# led_board.net
KiCad netlist of a schematic drawn in EAGLE
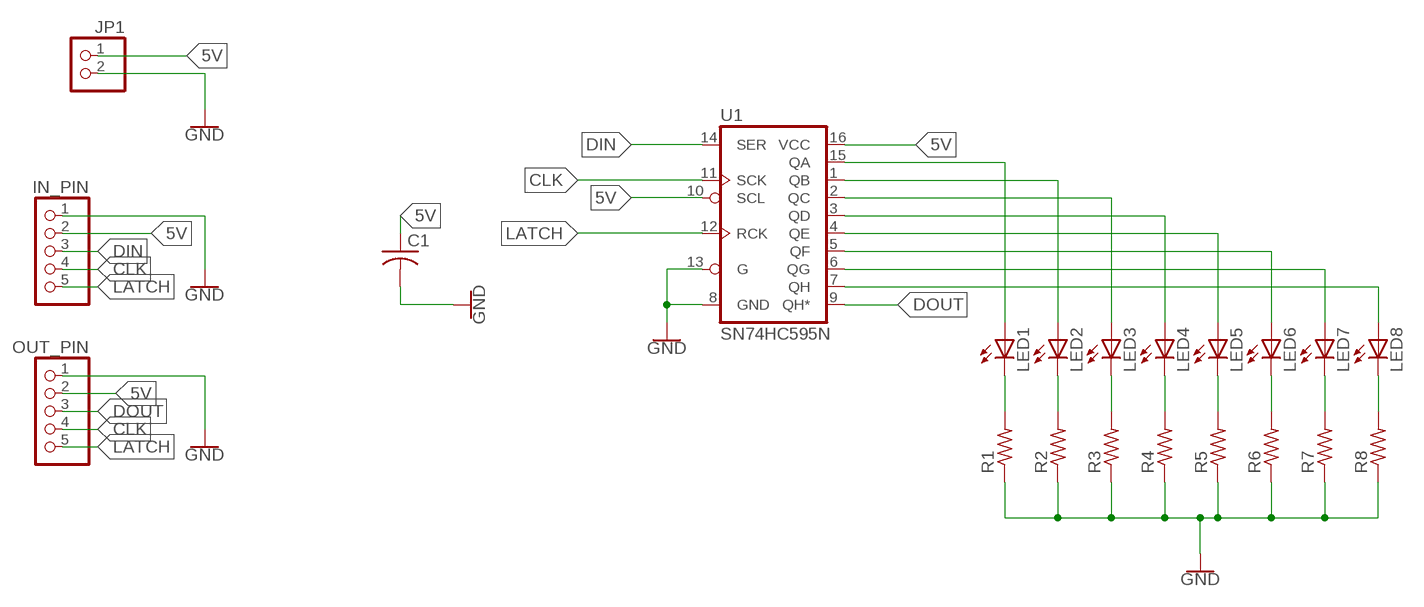
[diagram p0: schematic, sheet 1]

(export (version "E")
  (design (tool "Eeschema 10.0.6"))
  (components
    (comp (ref "C1")
      (value "C-US025-030X050")
      (footprint "eagle-import:C025-030X050")
      (libsource (lib "eagle-import") (part "C-US025-030X050"))
    )
    (comp (ref "IN_PIN")
      (value "PINHD-1X5")
      (footprint "eagle-import:1X05")
      (libsource (lib "eagle-import") (part "PINHD-1X5"))
    )
    (comp (ref "JP1")
      (value "PINHD-1X2")
      (footprint "eagle-import:1X02")
      (libsource (lib "eagle-import") (part "PINHD-1X2"))
    )
    (comp (ref "LED1")
      (value "LED3MM")
      (footprint "eagle-import:LED3MM")
      (libsource (lib "eagle-import") (part "LED3MM"))
    )
    (comp (ref "LED2")
      (value "LED3MM")
      (footprint "eagle-import:LED3MM")
      (libsource (lib "eagle-import") (part "LED3MM"))
    )
    (comp (ref "LED3")
      (value "LED3MM")
      (footprint "eagle-import:LED3MM")
      (libsource (lib "eagle-import") (part "LED3MM"))
    )
    (comp (ref "LED4")
      (value "LED3MM")
      (footprint "eagle-import:LED3MM")
      (libsource (lib "eagle-import") (part "LED3MM"))
    )
    (comp (ref "LED5")
      (value "LED3MM")
      (footprint "eagle-import:LED3MM")
      (libsource (lib "eagle-import") (part "LED3MM"))
    )
    (comp (ref "LED6")
      (value "LED3MM")
      (footprint "eagle-import:LED3MM")
      (libsource (lib "eagle-import") (part "LED3MM"))
    )
    (comp (ref "LED7")
      (value "LED3MM")
      (footprint "eagle-import:LED3MM")
      (libsource (lib "eagle-import") (part "LED3MM"))
    )
    (comp (ref "LED8")
      (value "LED3MM")
      (footprint "eagle-import:LED3MM")
      (libsource (lib "eagle-import") (part "LED3MM"))
    )
    (comp (ref "OUT_PIN")
      (value "PINHD-1X5")
      (footprint "eagle-import:1X05")
      (libsource (lib "eagle-import") (part "PINHD-1X5"))
    )
    (comp (ref "R1")
      (value "R-US_0207/7")
      (footprint "eagle-import:0207_7")
      (libsource (lib "eagle-import") (part "R-US_0207/7"))
    )
    (comp (ref "R2")
      (value "R-US_0207/7")
      (footprint "eagle-import:0207_7")
      (libsource (lib "eagle-import") (part "R-US_0207/7"))
    )
    (comp (ref "R3")
      (value "R-US_0207/7")
      (footprint "eagle-import:0207_7")
      (libsource (lib "eagle-import") (part "R-US_0207/7"))
    )
    (comp (ref "R4")
      (value "R-US_0207/7")
      (footprint "eagle-import:0207_7")
      (libsource (lib "eagle-import") (part "R-US_0207/7"))
    )
    (comp (ref "R5")
      (value "R-US_0207/7")
      (footprint "eagle-import:0207_7")
      (libsource (lib "eagle-import") (part "R-US_0207/7"))
    )
    (comp (ref "R6")
      (value "R-US_0207/7")
      (footprint "eagle-import:0207_7")
      (libsource (lib "eagle-import") (part "R-US_0207/7"))
    )
    (comp (ref "R7")
      (value "R-US_0207/7")
      (footprint "eagle-import:0207_7")
      (libsource (lib "eagle-import") (part "R-US_0207/7"))
    )
    (comp (ref "R8")
      (value "R-US_0207/7")
      (footprint "eagle-import:0207_7")
      (libsource (lib "eagle-import") (part "R-US_0207/7"))
    )
    (comp (ref "U1")
      (value "SN74HC595N")
      (footprint "eagle-import:DIP16")
      (libsource (lib "eagle-import") (part "74595NHC"))
    )
  )
  (nets
    (net (code "1") (name "5V") (class "Default")
      (node (ref "C1") (pin "1") (pinfunction "1_1") (pintype "passive"))
      (node (ref "IN_PIN") (pin "2") (pinfunction "2_2") (pintype "passive"))
      (node (ref "JP1") (pin "1") (pinfunction "1_1") (pintype "passive"))
      (node (ref "OUT_PIN") (pin "2") (pinfunction "2_2") (pintype "passive"))
      (node (ref "U1") (pin "10") (pinfunction "SCL_10") (pintype "input"))
      (node (ref "U1") (pin "16") (pinfunction "VCC_16") (pintype "power_in"))
    )
    (net (code "2") (name "CLK") (class "Default")
      (node (ref "IN_PIN") (pin "4") (pinfunction "4_4") (pintype "passive"))
      (node (ref "OUT_PIN") (pin "4") (pinfunction "4_4") (pintype "passive"))
      (node (ref "U1") (pin "11") (pinfunction "SCK_11") (pintype "input"))
    )
    (net (code "3") (name "DIN") (class "Default")
      (node (ref "IN_PIN") (pin "3") (pinfunction "3_3") (pintype "passive"))
      (node (ref "U1") (pin "14") (pinfunction "SER_14") (pintype "input"))
    )
    (net (code "4") (name "DOUT") (class "Default")
      (node (ref "OUT_PIN") (pin "3") (pinfunction "3_3") (pintype "passive"))
      (node (ref "U1") (pin "9") (pinfunction "QH*_9") (pintype "tri_state"))
    )
    (net (code "5") (name "GND") (class "Default")
      (node (ref "C1") (pin "2") (pinfunction "2_2") (pintype "passive"))
      (node (ref "IN_PIN") (pin "1") (pinfunction "1_1") (pintype "passive"))
      (node (ref "JP1") (pin "2") (pinfunction "2_2") (pintype "passive"))
      (node (ref "OUT_PIN") (pin "1") (pinfunction "1_1") (pintype "passive"))
      (node (ref "R1") (pin "1") (pinfunction "1_1") (pintype "passive"))
      (node (ref "R2") (pin "1") (pinfunction "1_1") (pintype "passive"))
      (node (ref "R3") (pin "1") (pinfunction "1_1") (pintype "passive"))
      (node (ref "R4") (pin "1") (pinfunction "1_1") (pintype "passive"))
      (node (ref "R5") (pin "1") (pinfunction "1_1") (pintype "passive"))
      (node (ref "R6") (pin "1") (pinfunction "1_1") (pintype "passive"))
      (node (ref "R7") (pin "1") (pinfunction "1_1") (pintype "passive"))
      (node (ref "R8") (pin "1") (pinfunction "1_1") (pintype "passive"))
      (node (ref "U1") (pin "13") (pinfunction "G_13") (pintype "input"))
      (node (ref "U1") (pin "8") (pinfunction "GND_8") (pintype "power_in"))
    )
    (net (code "6") (name "LATCH") (class "Default")
      (node (ref "IN_PIN") (pin "5") (pinfunction "5_5") (pintype "passive"))
      (node (ref "OUT_PIN") (pin "5") (pinfunction "5_5") (pintype "passive"))
      (node (ref "U1") (pin "12") (pinfunction "RCK_12") (pintype "input"))
    )
    (net (code "7") (name "Net-(LED1-C)") (class "Default")
      (node (ref "LED1") (pin "K") (pinfunction "C_K") (pintype "passive"))
      (node (ref "R1") (pin "2") (pinfunction "2_2") (pintype "passive"))
    )
    (net (code "8") (name "Net-(LED2-C)") (class "Default")
      (node (ref "LED2") (pin "K") (pinfunction "C_K") (pintype "passive"))
      (node (ref "R2") (pin "2") (pinfunction "2_2") (pintype "passive"))
    )
    (net (code "9") (name "Net-(LED3-C)") (class "Default")
      (node (ref "LED3") (pin "K") (pinfunction "C_K") (pintype "passive"))
      (node (ref "R3") (pin "2") (pinfunction "2_2") (pintype "passive"))
    )
    (net (code "10") (name "Net-(LED4-C)") (class "Default")
      (node (ref "LED4") (pin "K") (pinfunction "C_K") (pintype "passive"))
      (node (ref "R4") (pin "2") (pinfunction "2_2") (pintype "passive"))
    )
    (net (code "11") (name "Net-(LED5-C)") (class "Default")
      (node (ref "LED5") (pin "K") (pinfunction "C_K") (pintype "passive"))
      (node (ref "R5") (pin "2") (pinfunction "2_2") (pintype "passive"))
    )
    (net (code "12") (name "Net-(LED6-C)") (class "Default")
      (node (ref "LED6") (pin "K") (pinfunction "C_K") (pintype "passive"))
      (node (ref "R6") (pin "2") (pinfunction "2_2") (pintype "passive"))
    )
    (net (code "13") (name "Net-(LED7-C)") (class "Default")
      (node (ref "LED7") (pin "K") (pinfunction "C_K") (pintype "passive"))
      (node (ref "R7") (pin "2") (pinfunction "2_2") (pintype "passive"))
    )
    (net (code "14") (name "Net-(LED8-C)") (class "Default")
      (node (ref "LED8") (pin "K") (pinfunction "C_K") (pintype "passive"))
      (node (ref "R8") (pin "2") (pinfunction "2_2") (pintype "passive"))
    )
    (net (code "15") (name "Net-(U1-QA)") (class "Default")
      (node (ref "LED1") (pin "A") (pinfunction "A_A") (pintype "passive"))
      (node (ref "U1") (pin "15") (pinfunction "QA_15") (pintype "tri_state"))
    )
    (net (code "16") (name "Net-(U1-QB)") (class "Default")
      (node (ref "LED2") (pin "A") (pinfunction "A_A") (pintype "passive"))
      (node (ref "U1") (pin "1") (pinfunction "QB_1") (pintype "tri_state"))
    )
    (net (code "17") (name "Net-(U1-QC)") (class "Default")
      (node (ref "LED3") (pin "A") (pinfunction "A_A") (pintype "passive"))
      (node (ref "U1") (pin "2") (pinfunction "QC_2") (pintype "tri_state"))
    )
    (net (code "18") (name "Net-(U1-QD)") (class "Default")
      (node (ref "LED4") (pin "A") (pinfunction "A_A") (pintype "passive"))
      (node (ref "U1") (pin "3") (pinfunction "QD_3") (pintype "tri_state"))
    )
    (net (code "19") (name "Net-(U1-QE)") (class "Default")
      (node (ref "LED5") (pin "A") (pinfunction "A_A") (pintype "passive"))
      (node (ref "U1") (pin "4") (pinfunction "QE_4") (pintype "tri_state"))
    )
    (net (code "20") (name "Net-(U1-QF)") (class "Default")
      (node (ref "LED6") (pin "A") (pinfunction "A_A") (pintype "passive"))
      (node (ref "U1") (pin "5") (pinfunction "QF_5") (pintype "tri_state"))
    )
    (net (code "21") (name "Net-(U1-QG)") (class "Default")
      (node (ref "LED7") (pin "A") (pinfunction "A_A") (pintype "passive"))
      (node (ref "U1") (pin "6") (pinfunction "QG_6") (pintype "tri_state"))
    )
    (net (code "22") (name "Net-(U1-QH)") (class "Default")
      (node (ref "LED8") (pin "A") (pinfunction "A_A") (pintype "passive"))
      (node (ref "U1") (pin "7") (pinfunction "QH_7") (pintype "tri_state"))
    )
  )
)
